# R2P_DCM_v2.net
KiCad netlist of a schematic drawn in EAGLE
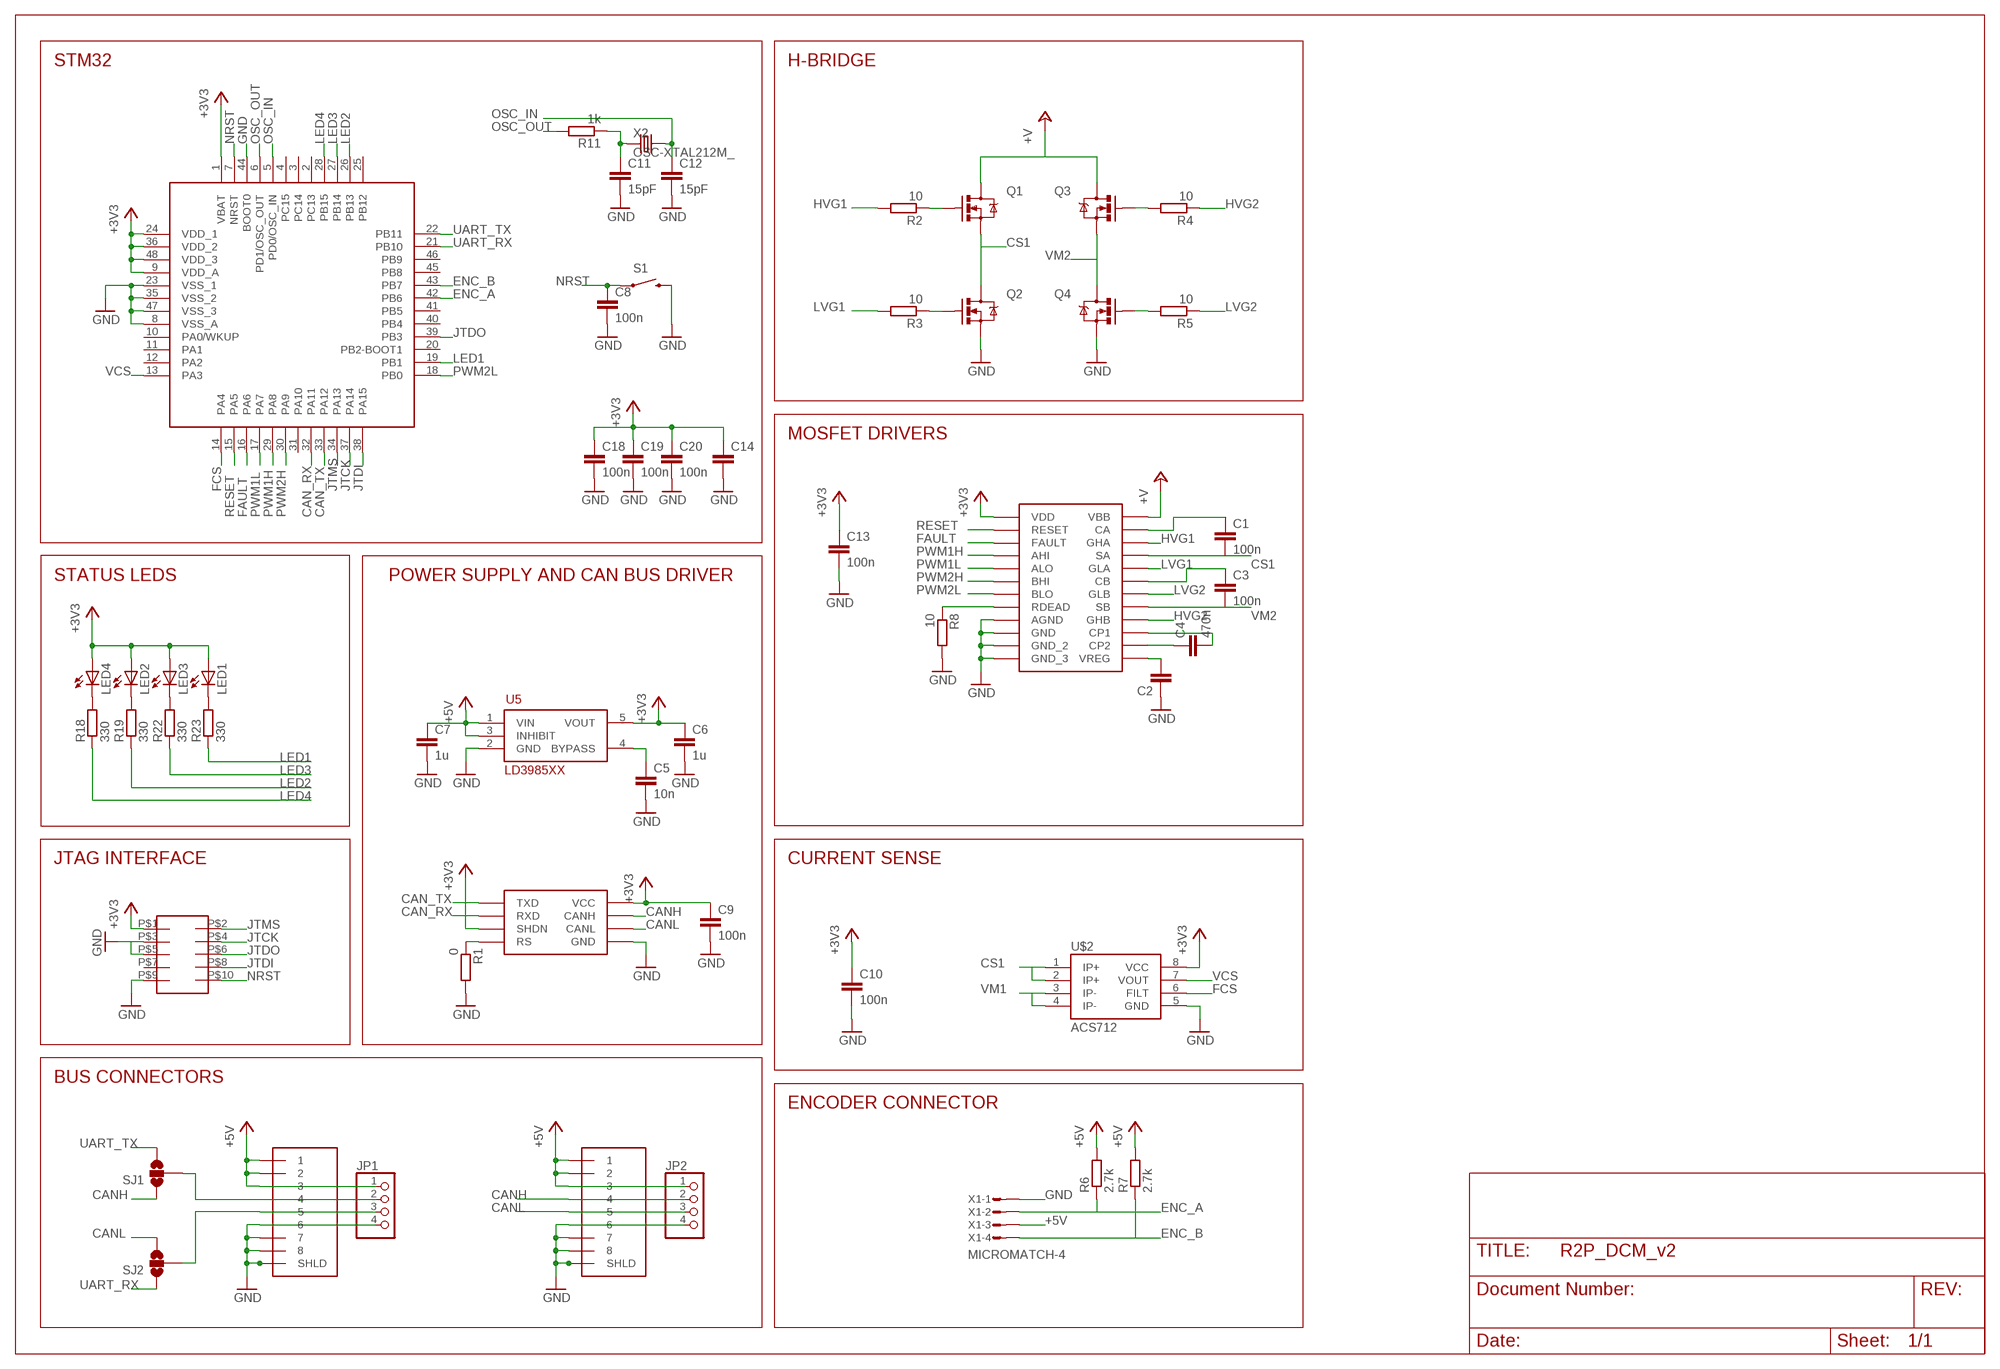
[diagram p0: schematic, sheet 1]

(export (version "E")
  (design (tool "Eeschema 10.0.6"))
  (components
    (comp (ref "1")
      (value "RJ45-43860")
      (footprint "eagle-import:0438600010")
      (libsource (lib "eagle-import") (part "RJ45-43860"))
    )
    (comp (ref "2")
      (value "RJ45-43860")
      (footprint "eagle-import:0438600010")
      (libsource (lib "eagle-import") (part "RJ45-43860"))
    )
    (comp (ref "C1")
      (value "100n")
      (footprint "eagle-import:C0603")
      (libsource (lib "eagle-import") (part "C-EUC0603"))
    )
    (comp (ref "C2")
      (value "C-EUC0805")
      (footprint "eagle-import:C0805")
      (libsource (lib "eagle-import") (part "C-EUC0805"))
    )
    (comp (ref "C3")
      (value "100n")
      (footprint "eagle-import:C0603")
      (libsource (lib "eagle-import") (part "C-EUC0603"))
    )
    (comp (ref "C4")
      (value "470n")
      (footprint "eagle-import:C0603")
      (libsource (lib "eagle-import") (part "C-EUC0603"))
    )
    (comp (ref "C5")
      (value "10n")
      (footprint "eagle-import:C0603")
      (libsource (lib "eagle-import") (part "C-EUC0603"))
    )
    (comp (ref "C6")
      (value "1u")
      (footprint "eagle-import:C0603")
      (libsource (lib "eagle-import") (part "C-EUC0603"))
    )
    (comp (ref "C7")
      (value "1u")
      (footprint "eagle-import:C0603")
      (libsource (lib "eagle-import") (part "C-EUC0603"))
    )
    (comp (ref "C8")
      (value "100n")
      (footprint "eagle-import:C0603")
      (libsource (lib "eagle-import") (part "C-EUC0603"))
    )
    (comp (ref "C9")
      (value "100n")
      (footprint "eagle-import:C0603")
      (libsource (lib "eagle-import") (part "C-EUC0603"))
    )
    (comp (ref "C10")
      (value "100n")
      (footprint "eagle-import:C0603")
      (libsource (lib "eagle-import") (part "C-EUC0603"))
    )
    (comp (ref "C11")
      (value "15pF")
      (footprint "eagle-import:C0603")
      (libsource (lib "eagle-import") (part "C-EUC0603"))
    )
    (comp (ref "C12")
      (value "15pF")
      (footprint "eagle-import:C0603")
      (libsource (lib "eagle-import") (part "C-EUC0603"))
    )
    (comp (ref "C13")
      (value "100n")
      (footprint "eagle-import:C0603")
      (libsource (lib "eagle-import") (part "C-EUC0603"))
    )
    (comp (ref "C14")
      (value "C-EUC0805")
      (footprint "eagle-import:C0805")
      (libsource (lib "eagle-import") (part "C-EUC0805"))
    )
    (comp (ref "C18")
      (value "100n")
      (footprint "eagle-import:C0603")
      (libsource (lib "eagle-import") (part "C-EUC0603"))
    )
    (comp (ref "C19")
      (value "100n")
      (footprint "eagle-import:C0603")
      (libsource (lib "eagle-import") (part "C-EUC0603"))
    )
    (comp (ref "C20")
      (value "100n")
      (footprint "eagle-import:C0603")
      (libsource (lib "eagle-import") (part "C-EUC0603"))
    )
    (comp (ref "JP1")
      (value "PINHD-1X4/90")
      (footprint "eagle-import:1X04_90")
      (libsource (lib "eagle-import") (part "PINHD-1X4/90"))
    )
    (comp (ref "JP2")
      (value "PINHD-1X4/90")
      (footprint "eagle-import:1X04_90")
      (libsource (lib "eagle-import") (part "PINHD-1X4/90"))
    )
    (comp (ref "LED1")
      (value "LEDCHIPLED_0805")
      (footprint "eagle-import:CHIPLED_0805")
      (libsource (lib "eagle-import") (part "LEDCHIPLED_0805"))
    )
    (comp (ref "LED2")
      (value "LEDCHIPLED_0805")
      (footprint "eagle-import:CHIPLED_0805")
      (libsource (lib "eagle-import") (part "LEDCHIPLED_0805"))
    )
    (comp (ref "LED3")
      (value "LEDCHIPLED_0805")
      (footprint "eagle-import:CHIPLED_0805")
      (libsource (lib "eagle-import") (part "LEDCHIPLED_0805"))
    )
    (comp (ref "LED4")
      (value "LEDCHIPLED_0805")
      (footprint "eagle-import:CHIPLED_0805")
      (libsource (lib "eagle-import") (part "LEDCHIPLED_0805"))
    )
    (comp (ref "Q1")
      (value "MOSFET-NCHANNELFDD8580")
      (footprint "eagle-import:DPAK")
      (libsource (lib "eagle-import") (part "MOSFET-NCHANNELFDD8580"))
    )
    (comp (ref "Q2")
      (value "MOSFET-NCHANNELFDD8580")
      (footprint "eagle-import:DPAK")
      (libsource (lib "eagle-import") (part "MOSFET-NCHANNELFDD8580"))
    )
    (comp (ref "Q3")
      (value "MOSFET-NCHANNELFDD8580")
      (footprint "eagle-import:DPAK")
      (libsource (lib "eagle-import") (part "MOSFET-NCHANNELFDD8580"))
    )
    (comp (ref "Q4")
      (value "MOSFET-NCHANNELFDD8580")
      (footprint "eagle-import:DPAK")
      (libsource (lib "eagle-import") (part "MOSFET-NCHANNELFDD8580"))
    )
    (comp (ref "R1")
      (value "0")
      (footprint "eagle-import:R0603")
      (libsource (lib "eagle-import") (part "R-EU_R0603"))
    )
    (comp (ref "R2")
      (value "10")
      (footprint "eagle-import:R0603")
      (libsource (lib "eagle-import") (part "R-EU_R0603"))
    )
    (comp (ref "R3")
      (value "10")
      (footprint "eagle-import:R0603")
      (libsource (lib "eagle-import") (part "R-EU_R0603"))
    )
    (comp (ref "R4")
      (value "10")
      (footprint "eagle-import:R0603")
      (libsource (lib "eagle-import") (part "R-EU_R0603"))
    )
    (comp (ref "R5")
      (value "10")
      (footprint "eagle-import:R0603")
      (libsource (lib "eagle-import") (part "R-EU_R0603"))
    )
    (comp (ref "R6")
      (value "2.7k")
      (footprint "eagle-import:R0603")
      (libsource (lib "eagle-import") (part "R-EU_R0603"))
    )
    (comp (ref "R7")
      (value "2.7k")
      (footprint "eagle-import:R0603")
      (libsource (lib "eagle-import") (part "R-EU_R0603"))
    )
    (comp (ref "R8")
      (value "10")
      (footprint "eagle-import:R0603")
      (libsource (lib "eagle-import") (part "R-EU_R0603"))
    )
    (comp (ref "R11")
      (value "1k")
      (footprint "eagle-import:R0603")
      (libsource (lib "eagle-import") (part "R-EU_R0603"))
    )
    (comp (ref "R18")
      (value "330")
      (footprint "eagle-import:R0603")
      (libsource (lib "eagle-import") (part "R-EU_R0603"))
    )
    (comp (ref "R19")
      (value "330")
      (footprint "eagle-import:R0603")
      (libsource (lib "eagle-import") (part "R-EU_R0603"))
    )
    (comp (ref "R22")
      (value "330")
      (footprint "eagle-import:R0603")
      (libsource (lib "eagle-import") (part "R-EU_R0603"))
    )
    (comp (ref "R23")
      (value "330")
      (footprint "eagle-import:R0603")
      (libsource (lib "eagle-import") (part "R-EU_R0603"))
    )
    (comp (ref "S1")
      (value "SWITCH-MOMENTARY-2-SMD-1101NE")
      (footprint "eagle-import:TACTILE-SWITCH-1101NE")
      (libsource (lib "eagle-import") (part "SWITCH-MOMENTARY-2-SMD-1101NE"))
    )
    (comp (ref "SJ1")
      (value "SOLDERJUMPER_2WAYPASTE1&2")
      (footprint "eagle-import:SJ_3_PASTE1&2")
      (libsource (lib "eagle-import") (part "SOLDERJUMPER_2WAYPASTE1&2"))
    )
    (comp (ref "SJ2")
      (value "SOLDERJUMPER_2WAYPASTE1&2")
      (footprint "eagle-import:SJ_3_PASTE1&2")
      (libsource (lib "eagle-import") (part "SOLDERJUMPER_2WAYPASTE1&2"))
    )
    (comp (ref "SOT1")
      (value "MAX3051")
      (footprint "eagle-import:SOT23-8L")
      (libsource (lib "eagle-import") (part "MAX3051"))
    )
    (comp (ref "U$1")
      (value "A4940")
      (footprint "eagle-import:TSSOP24")
      (libsource (lib "eagle-import") (part "A4940"))
    )
    (comp (ref "U$2")
      (value "ACS712")
      (footprint "eagle-import:SO08")
      (libsource (lib "eagle-import") (part "ACS712"))
    )
    (comp (ref "U$4")
      (value "FTSH-105")
      (footprint "eagle-import:FTSH-105")
      (libsource (lib "eagle-import") (part "FTSH-105"))
    )
    (comp (ref "U1")
      (value "STM32F103CX")
      (footprint "eagle-import:LQFP48")
      (libsource (lib "eagle-import") (part "STM32F103CX"))
    )
    (comp (ref "U5")
      (value "LD3985XX")
      (footprint "eagle-import:SOT23-5L")
      (libsource (lib "eagle-import") (part "LD3985XX"))
    )
    (comp (ref "X1")
      (value "MICROMATCH-4")
      (footprint "eagle-import:MICROMATCH-4")
      (libsource (lib "eagle-import") (part "MICROMATCH-4"))
    )
    (comp (ref "X2")
      (value "OSC-XTAL212M_")
      (footprint "eagle-import:4X6")
      (libsource (lib "eagle-import") (part "OSC-XTAL212M_"))
    )
  )
  (nets
    (net (code "1") (name "+3V3") (class "Default")
      (node (ref "C10") (pin "1") (pinfunction "1_1") (pintype "passive"))
      (node (ref "C13") (pin "1") (pinfunction "1_1") (pintype "passive"))
      (node (ref "C14") (pin "1") (pinfunction "1_1") (pintype "passive"))
      (node (ref "C18") (pin "1") (pinfunction "1_1") (pintype "passive"))
      (node (ref "C19") (pin "1") (pinfunction "1_1") (pintype "passive"))
      (node (ref "C20") (pin "1") (pinfunction "1_1") (pintype "passive"))
      (node (ref "C6") (pin "1") (pinfunction "1_1") (pintype "passive"))
      (node (ref "C9") (pin "1") (pinfunction "1_1") (pintype "passive"))
      (node (ref "LED1") (pin "A") (pinfunction "A_A") (pintype "passive"))
      (node (ref "LED2") (pin "A") (pinfunction "A_A") (pintype "passive"))
      (node (ref "LED3") (pin "A") (pinfunction "A_A") (pintype "passive"))
      (node (ref "LED4") (pin "A") (pinfunction "A_A") (pintype "passive"))
      (node (ref "SOT1") (pin "P$3") (pinfunction "VCC_P$3") (pintype "bidirectional"))
      (node (ref "SOT1") (pin "P$5") (pinfunction "SHDN_P$5") (pintype "bidirectional"))
      (node (ref "U$1") (pin "21") (pinfunction "VDD_21") (pintype "bidirectional"))
      (node (ref "U$2") (pin "8") (pinfunction "VCC_8") (pintype "bidirectional"))
      (node (ref "U$4") (pin "P$1") (pinfunction "P$1_P$1") (pintype "bidirectional"))
      (node (ref "U1") (pin "1") (pinfunction "VBAT_1") (pintype "bidirectional"))
      (node (ref "U1") (pin "24") (pinfunction "VDD_1_24") (pintype "bidirectional"))
      (node (ref "U1") (pin "36") (pinfunction "VDD_2_36") (pintype "bidirectional"))
      (node (ref "U1") (pin "48") (pinfunction "VDD_3_48") (pintype "bidirectional"))
      (node (ref "U1") (pin "9") (pinfunction "VDD_A_9") (pintype "bidirectional"))
      (node (ref "U5") (pin "5") (pinfunction "VOUT_5") (pintype "bidirectional"))
    )
    (net (code "2") (name "+5V") (class "Default")
      (node (ref "1") (pin "P$1") (pinfunction "1_P$1") (pintype "bidirectional"))
      (node (ref "1") (pin "P$2") (pinfunction "2_P$2") (pintype "bidirectional"))
      (node (ref "1") (pin "P$3") (pinfunction "3_P$3") (pintype "bidirectional"))
      (node (ref "2") (pin "P$1") (pinfunction "1_P$1") (pintype "bidirectional"))
      (node (ref "2") (pin "P$2") (pinfunction "2_P$2") (pintype "bidirectional"))
      (node (ref "2") (pin "P$3") (pinfunction "3_P$3") (pintype "bidirectional"))
      (node (ref "C7") (pin "1") (pinfunction "1_1") (pintype "passive"))
      (node (ref "JP1") (pin "1") (pinfunction "1_1") (pintype "passive"))
      (node (ref "JP2") (pin "1") (pinfunction "1_1") (pintype "passive"))
      (node (ref "R6") (pin "2") (pinfunction "2_2") (pintype "passive"))
      (node (ref "R7") (pin "2") (pinfunction "2_2") (pintype "passive"))
      (node (ref "U5") (pin "1") (pinfunction "VIN_1") (pintype "bidirectional"))
      (node (ref "U5") (pin "3") (pinfunction "INHIBIT_3") (pintype "bidirectional"))
      (node (ref "X1") (pin "3") (pinfunction "S_3") (pintype "passive"))
    )
    (net (code "3") (name "+V") (class "Default")
      (node (ref "Q1") (pin "4") (pinfunction "D_4") (pintype "passive"))
      (node (ref "Q3") (pin "4") (pinfunction "D_4") (pintype "passive"))
      (node (ref "U$1") (pin "12") (pinfunction "VBB_12") (pintype "bidirectional"))
    )
    (net (code "4") (name "/CANH") (class "Default")
      (node (ref "2") (pin "P$4") (pinfunction "4_P$4") (pintype "bidirectional"))
      (node (ref "JP2") (pin "2") (pinfunction "2_2") (pintype "passive"))
      (node (ref "SJ1") (pin "1") (pinfunction "1_1") (pintype "passive"))
      (node (ref "SOT1") (pin "P$7") (pinfunction "CANH_P$7") (pintype "bidirectional"))
    )
    (net (code "5") (name "/CANL") (class "Default")
      (node (ref "2") (pin "P$5") (pinfunction "5_P$5") (pintype "bidirectional"))
      (node (ref "JP2") (pin "3") (pinfunction "3_3") (pintype "passive"))
      (node (ref "SJ2") (pin "3") (pinfunction "3_3") (pintype "passive"))
      (node (ref "SOT1") (pin "P$6") (pinfunction "CANL_P$6") (pintype "bidirectional"))
    )
    (net (code "6") (name "/CAN_RX") (class "Default")
      (node (ref "SOT1") (pin "P$4") (pinfunction "RXD_P$4") (pintype "bidirectional"))
      (node (ref "U1") (pin "32") (pinfunction "PA11_32") (pintype "bidirectional"))
    )
    (net (code "7") (name "/CAN_TX") (class "Default")
      (node (ref "SOT1") (pin "P$1") (pinfunction "TXD_P$1") (pintype "bidirectional"))
      (node (ref "U1") (pin "33") (pinfunction "PA12_33") (pintype "bidirectional"))
    )
    (net (code "8") (name "/CS1") (class "Default")
      (node (ref "C1") (pin "2") (pinfunction "2_2") (pintype "passive"))
      (node (ref "Q1") (pin "3") (pinfunction "S_3") (pintype "passive"))
      (node (ref "Q2") (pin "4") (pinfunction "D_4") (pintype "passive"))
      (node (ref "U$1") (pin "10") (pinfunction "SA_10") (pintype "bidirectional"))
      (node (ref "U$2") (pin "1") (pinfunction "IP+_1") (pintype "bidirectional"))
      (node (ref "U$2") (pin "2") (pinfunction "IP+_2") (pintype "bidirectional"))
    )
    (net (code "9") (name "/ENC_A") (class "Default")
      (node (ref "R6") (pin "1") (pinfunction "1_1") (pintype "passive"))
      (node (ref "U1") (pin "42") (pinfunction "PB6_42") (pintype "bidirectional"))
      (node (ref "X1") (pin "2") (pinfunction "S_2") (pintype "passive"))
    )
    (net (code "10") (name "/ENC_B") (class "Default")
      (node (ref "R7") (pin "1") (pinfunction "1_1") (pintype "passive"))
      (node (ref "U1") (pin "43") (pinfunction "PB7_43") (pintype "bidirectional"))
      (node (ref "X1") (pin "4") (pinfunction "S_4") (pintype "passive"))
    )
    (net (code "11") (name "/FAULT") (class "Default")
      (node (ref "U$1") (pin "24") (pinfunction "FAULT_24") (pintype "bidirectional"))
      (node (ref "U1") (pin "16") (pinfunction "PA6_16") (pintype "bidirectional"))
    )
    (net (code "12") (name "/FCS") (class "Default")
      (node (ref "U$2") (pin "6") (pinfunction "FILT_6") (pintype "bidirectional"))
      (node (ref "U1") (pin "14") (pinfunction "PA4_14") (pintype "bidirectional"))
    )
    (net (code "13") (name "/HVG1") (class "Default")
      (node (ref "R2") (pin "2") (pinfunction "2_2") (pintype "passive"))
      (node (ref "U$1") (pin "9") (pinfunction "GHA_9") (pintype "bidirectional"))
    )
    (net (code "14") (name "/HVG2") (class "Default")
      (node (ref "R4") (pin "1") (pinfunction "1_1") (pintype "passive"))
      (node (ref "U$1") (pin "5") (pinfunction "GHB_5") (pintype "bidirectional"))
    )
    (net (code "15") (name "/JTCK") (class "Default")
      (node (ref "U$4") (pin "P$4") (pinfunction "P$4_P$4") (pintype "bidirectional"))
      (node (ref "U1") (pin "37") (pinfunction "PA14_37") (pintype "bidirectional"))
    )
    (net (code "16") (name "/JTDI") (class "Default")
      (node (ref "U$4") (pin "P$8") (pinfunction "P$8_P$8") (pintype "bidirectional"))
      (node (ref "U1") (pin "38") (pinfunction "PA15_38") (pintype "bidirectional"))
    )
    (net (code "17") (name "/JTDO") (class "Default")
      (node (ref "U$4") (pin "P$6") (pinfunction "P$6_P$6") (pintype "bidirectional"))
      (node (ref "U1") (pin "39") (pinfunction "PB3_39") (pintype "bidirectional"))
    )
    (net (code "18") (name "/JTMS") (class "Default")
      (node (ref "U$4") (pin "P$2") (pinfunction "P$2_P$2") (pintype "bidirectional"))
      (node (ref "U1") (pin "34") (pinfunction "PA13_34") (pintype "bidirectional"))
    )
    (net (code "19") (name "/LED1") (class "Default")
      (node (ref "R23") (pin "1") (pinfunction "1_1") (pintype "passive"))
      (node (ref "U1") (pin "19") (pinfunction "PB1_19") (pintype "bidirectional"))
    )
    (net (code "20") (name "/LED2") (class "Default")
      (node (ref "R19") (pin "1") (pinfunction "1_1") (pintype "passive"))
      (node (ref "U1") (pin "26") (pinfunction "PB13_26") (pintype "bidirectional"))
    )
    (net (code "21") (name "/LED3") (class "Default")
      (node (ref "R22") (pin "1") (pinfunction "1_1") (pintype "passive"))
      (node (ref "U1") (pin "27") (pinfunction "PB14_27") (pintype "bidirectional"))
    )
    (net (code "22") (name "/LED4") (class "Default")
      (node (ref "R18") (pin "1") (pinfunction "1_1") (pintype "passive"))
      (node (ref "U1") (pin "28") (pinfunction "PB15_28") (pintype "bidirectional"))
    )
    (net (code "23") (name "/LVG1") (class "Default")
      (node (ref "R3") (pin "2") (pinfunction "2_2") (pintype "passive"))
      (node (ref "U$1") (pin "11") (pinfunction "GLA_11") (pintype "bidirectional"))
    )
    (net (code "24") (name "/LVG2") (class "Default")
      (node (ref "R5") (pin "1") (pinfunction "1_1") (pintype "passive"))
      (node (ref "U$1") (pin "3") (pinfunction "GLB_3") (pintype "bidirectional"))
    )
    (net (code "25") (name "/NRST") (class "Default")
      (node (ref "C8") (pin "1") (pinfunction "1_1") (pintype "passive"))
      (node (ref "S1") (pin "P$1") (pinfunction "1_P$1") (pintype "passive"))
      (node (ref "U$4") (pin "P$10") (pinfunction "P$10_P$10") (pintype "bidirectional"))
      (node (ref "U1") (pin "7") (pinfunction "NRST_7") (pintype "bidirectional"))
    )
    (net (code "26") (name "/OSC_IN") (class "Default")
      (node (ref "C12") (pin "1") (pinfunction "1_1") (pintype "passive"))
      (node (ref "U1") (pin "5") (pinfunction "PD0/OSC_IN_5") (pintype "bidirectional"))
      (node (ref "X2") (pin "2") (pinfunction "X2_2") (pintype "bidirectional"))
    )
    (net (code "27") (name "/OSC_OUT") (class "Default")
      (node (ref "R11") (pin "2") (pinfunction "2_2") (pintype "passive"))
      (node (ref "U1") (pin "6") (pinfunction "PD1/OSC_OUT_6") (pintype "bidirectional"))
    )
    (net (code "28") (name "/PWM1H") (class "Default")
      (node (ref "U$1") (pin "20") (pinfunction "AHI_20") (pintype "bidirectional"))
      (node (ref "U1") (pin "29") (pinfunction "PA8_29") (pintype "bidirectional"))
    )
    (net (code "29") (name "/PWM1L") (class "Default")
      (node (ref "U$1") (pin "19") (pinfunction "ALO_19") (pintype "bidirectional"))
      (node (ref "U1") (pin "17") (pinfunction "PA7_17") (pintype "bidirectional"))
    )
    (net (code "30") (name "/PWM2H") (class "Default")
      (node (ref "U$1") (pin "18") (pinfunction "BHI_18") (pintype "bidirectional"))
      (node (ref "U1") (pin "30") (pinfunction "PA9_30") (pintype "bidirectional"))
    )
    (net (code "31") (name "/PWM2L") (class "Default")
      (node (ref "U$1") (pin "17") (pinfunction "BLO_17") (pintype "bidirectional"))
      (node (ref "U1") (pin "18") (pinfunction "PB0_18") (pintype "bidirectional"))
    )
    (net (code "32") (name "/RESET") (class "Default")
      (node (ref "U$1") (pin "1") (pinfunction "RESET_1") (pintype "bidirectional"))
      (node (ref "U1") (pin "15") (pinfunction "PA5_15") (pintype "bidirectional"))
    )
    (net (code "33") (name "/UART_RX") (class "Default")
      (node (ref "SJ2") (pin "1") (pinfunction "1_1") (pintype "passive"))
      (node (ref "U1") (pin "21") (pinfunction "PB10_21") (pintype "bidirectional"))
    )
    (net (code "34") (name "/UART_TX") (class "Default")
      (node (ref "SJ1") (pin "3") (pinfunction "3_3") (pintype "passive"))
      (node (ref "U1") (pin "22") (pinfunction "PB11_22") (pintype "bidirectional"))
    )
    (net (code "35") (name "/VCS") (class "Default")
      (node (ref "U$2") (pin "7") (pinfunction "VOUT_7") (pintype "bidirectional"))
      (node (ref "U1") (pin "13") (pinfunction "PA3_13") (pintype "bidirectional"))
    )
    (net (code "36") (name "/VM1") (class "Default")
      (node (ref "U$2") (pin "3") (pinfunction "IP-_3") (pintype "bidirectional"))
      (node (ref "U$2") (pin "4") (pinfunction "IP-_4") (pintype "bidirectional"))
    )
    (net (code "37") (name "/VM2") (class "Default")
      (node (ref "C3") (pin "2") (pinfunction "2_2") (pintype "passive"))
      (node (ref "Q3") (pin "3") (pinfunction "S_3") (pintype "passive"))
      (node (ref "Q4") (pin "4") (pinfunction "D_4") (pintype "passive"))
      (node (ref "U$1") (pin "4") (pinfunction "SB_4") (pintype "bidirectional"))
    )
    (net (code "38") (name "GND") (class "Default")
      (node (ref "1") (pin "P$10") (pinfunction "P$1_P$10") (pintype "power_in"))
      (node (ref "1") (pin "P$6") (pinfunction "6_P$6") (pintype "bidirectional"))
      (node (ref "1") (pin "P$7") (pinfunction "7_P$7") (pintype "bidirectional"))
      (node (ref "1") (pin "P$8") (pinfunction "8_P$8") (pintype "bidirectional"))
      (node (ref "1") (pin "P$9") (pinfunction "SHLD_P$9") (pintype "power_in"))
      (node (ref "2") (pin "P$10") (pinfunction "P$1_P$10") (pintype "power_in"))
      (node (ref "2") (pin "P$6") (pinfunction "6_P$6") (pintype "bidirectional"))
      (node (ref "2") (pin "P$7") (pinfunction "7_P$7") (pintype "bidirectional"))
      (node (ref "2") (pin "P$8") (pinfunction "8_P$8") (pintype "bidirectional"))
      (node (ref "2") (pin "P$9") (pinfunction "SHLD_P$9") (pintype "power_in"))
      (node (ref "C10") (pin "2") (pinfunction "2_2") (pintype "passive"))
      (node (ref "C11") (pin "2") (pinfunction "2_2") (pintype "passive"))
      (node (ref "C12") (pin "2") (pinfunction "2_2") (pintype "passive"))
      (node (ref "C13") (pin "2") (pinfunction "2_2") (pintype "passive"))
      (node (ref "C14") (pin "2") (pinfunction "2_2") (pintype "passive"))
      (node (ref "C18") (pin "2") (pinfunction "2_2") (pintype "passive"))
      (node (ref "C19") (pin "2") (pinfunction "2_2") (pintype "passive"))
      (node (ref "C2") (pin "1") (pinfunction "1_1") (pintype "passive"))
      (node (ref "C20") (pin "2") (pinfunction "2_2") (pintype "passive"))
      (node (ref "C5") (pin "2") (pinfunction "2_2") (pintype "passive"))
      (node (ref "C6") (pin "2") (pinfunction "2_2") (pintype "passive"))
      (node (ref "C7") (pin "2") (pinfunction "2_2") (pintype "passive"))
      (node (ref "C8") (pin "2") (pinfunction "2_2") (pintype "passive"))
      (node (ref "C9") (pin "2") (pinfunction "2_2") (pintype "passive"))
      (node (ref "JP1") (pin "4") (pinfunction "4_4") (pintype "passive"))
      (node (ref "JP2") (pin "4") (pinfunction "4_4") (pintype "passive"))
      (node (ref "Q2") (pin "3") (pinfunction "S_3") (pintype "passive"))
      (node (ref "Q4") (pin "3") (pinfunction "S_3") (pintype "passive"))
      (node (ref "R1") (pin "2") (pinfunction "2_2") (pintype "passive"))
      (node (ref "R8") (pin "2") (pinfunction "2_2") (pintype "passive"))
      (node (ref "S1") (pin "P$2") (pinfunction "2_P$2") (pintype "passive"))
      (node (ref "SOT1") (pin "P$2") (pinfunction "GND_P$2") (pintype "bidirectional"))
      (node (ref "U$1") (pin "15") (pinfunction "GND_2_15") (pintype "bidirectional"))
      (node (ref "U$1") (pin "16") (pinfunction "GND_3_16") (pintype "bidirectional"))
      (node (ref "U$1") (pin "2") (pinfunction "GND_2") (pintype "bidirectional"))
      (node (ref "U$1") (pin "22") (pinfunction "AGND_22") (pintype "bidirectional"))
      (node (ref "U$1") (pin "PAD") (pinfunction "GND_PAD") (pintype "bidirectional"))
      (node (ref "U$2") (pin "5") (pinfunction "GND_5") (pintype "bidirectional"))
      (node (ref "U$4") (pin "P$3") (pinfunction "P$3_P$3") (pintype "bidirectional"))
      (node (ref "U$4") (pin "P$9") (pinfunction "P$9_P$9") (pintype "bidirectional"))
      (node (ref "U1") (pin "23") (pinfunction "VSS_1_23") (pintype "bidirectional"))
      (node (ref "U1") (pin "35") (pinfunction "VSS_2_35") (pintype "bidirectional"))
      (node (ref "U1") (pin "44") (pinfunction "BOOT0_44") (pintype "bidirectional"))
      (node (ref "U1") (pin "47") (pinfunction "VSS_3_47") (pintype "bidirectional"))
      (node (ref "U1") (pin "8") (pinfunction "VSS_A_8") (pintype "bidirectional"))
      (node (ref "U5") (pin "2") (pinfunction "GND_2") (pintype "bidirectional"))
      (node (ref "X1") (pin "1") (pinfunction "S_1") (pintype "passive"))
    )
    (net (code "39") (name "Net-(1-4)") (class "Default")
      (node (ref "1") (pin "P$4") (pinfunction "4_P$4") (pintype "bidirectional"))
      (node (ref "JP1") (pin "2") (pinfunction "2_2") (pintype "passive"))
      (node (ref "SJ1") (pin "2") (pinfunction "2_2") (pintype "passive"))
    )
    (net (code "40") (name "Net-(1-5)") (class "Default")
      (node (ref "1") (pin "P$5") (pinfunction "5_P$5") (pintype "bidirectional"))
      (node (ref "JP1") (pin "3") (pinfunction "3_3") (pintype "passive"))
      (node (ref "SJ2") (pin "2") (pinfunction "2_2") (pintype "passive"))
    )
    (net (code "41") (name "Net-(LED1-PadC)") (class "Default")
      (node (ref "LED1") (pin "C") (pinfunction "C_C") (pintype "passive"))
      (node (ref "R23") (pin "2") (pinfunction "2_2") (pintype "passive"))
    )
    (net (code "42") (name "Net-(LED2-PadC)") (class "Default")
      (node (ref "LED2") (pin "C") (pinfunction "C_C") (pintype "passive"))
      (node (ref "R19") (pin "2") (pinfunction "2_2") (pintype "passive"))
    )
    (net (code "43") (name "Net-(LED3-PadC)") (class "Default")
      (node (ref "LED3") (pin "C") (pinfunction "C_C") (pintype "passive"))
      (node (ref "R22") (pin "2") (pinfunction "2_2") (pintype "passive"))
    )
    (net (code "44") (name "Net-(LED4-PadC)") (class "Default")
      (node (ref "LED4") (pin "C") (pinfunction "C_C") (pintype "passive"))
      (node (ref "R18") (pin "2") (pinfunction "2_2") (pintype "passive"))
    )
    (net (code "45") (name "Net-(Q1-G)") (class "Default")
      (node (ref "Q1") (pin "1") (pinfunction "G_1") (pintype "passive"))
      (node (ref "R2") (pin "1") (pinfunction "1_1") (pintype "passive"))
    )
    (net (code "46") (name "Net-(Q2-G)") (class "Default")
      (node (ref "Q2") (pin "1") (pinfunction "G_1") (pintype "passive"))
      (node (ref "R3") (pin "1") (pinfunction "1_1") (pintype "passive"))
    )
    (net (code "47") (name "Net-(Q3-G)") (class "Default")
      (node (ref "Q3") (pin "1") (pinfunction "G_1") (pintype "passive"))
      (node (ref "R4") (pin "2") (pinfunction "2_2") (pintype "passive"))
    )
    (net (code "48") (name "Net-(Q4-G)") (class "Default")
      (node (ref "Q4") (pin "1") (pinfunction "G_1") (pintype "passive"))
      (node (ref "R5") (pin "2") (pinfunction "2_2") (pintype "passive"))
    )
    (net (code "49") (name "Net-(SOT1-RS)") (class "Default")
      (node (ref "R1") (pin "1") (pinfunction "1_1") (pintype "passive"))
      (node (ref "SOT1") (pin "P$8") (pinfunction "RS_P$8") (pintype "bidirectional"))
    )
    (net (code "50") (name "Net-(U$1-CA)") (class "Default")
      (node (ref "C1") (pin "1") (pinfunction "1_1") (pintype "passive"))
      (node (ref "U$1") (pin "8") (pinfunction "CA_8") (pintype "bidirectional"))
    )
    (net (code "51") (name "Net-(U$1-CB)") (class "Default")
      (node (ref "C3") (pin "1") (pinfunction "1_1") (pintype "passive"))
      (node (ref "U$1") (pin "6") (pinfunction "CB_6") (pintype "bidirectional"))
    )
    (net (code "52") (name "Net-(U$1-CP1)") (class "Default")
      (node (ref "C4") (pin "2") (pinfunction "2_2") (pintype "passive"))
      (node (ref "U$1") (pin "14") (pinfunction "CP1_14") (pintype "bidirectional"))
    )
    (net (code "53") (name "Net-(U$1-CP2)") (class "Default")
      (node (ref "C4") (pin "1") (pinfunction "1_1") (pintype "passive"))
      (node (ref "U$1") (pin "13") (pinfunction "CP2_13") (pintype "bidirectional"))
    )
    (net (code "54") (name "Net-(U$1-RDEAD)") (class "Default")
      (node (ref "R8") (pin "1") (pinfunction "1_1") (pintype "passive"))
      (node (ref "U$1") (pin "23") (pinfunction "RDEAD_23") (pintype "bidirectional"))
    )
    (net (code "55") (name "Net-(U$1-VREG)") (class "Default")
      (node (ref "C2") (pin "2") (pinfunction "2_2") (pintype "passive"))
      (node (ref "U$1") (pin "7") (pinfunction "VREG_7") (pintype "bidirectional"))
    )
    (net (code "56") (name "Net-(U5-BYPASS)") (class "Default")
      (node (ref "C5") (pin "1") (pinfunction "1_1") (pintype "passive"))
      (node (ref "U5") (pin "4") (pinfunction "BYPASS_4") (pintype "bidirectional"))
    )
    (net (code "57") (name "Net-(X2-X1)") (class "Default")
      (node (ref "C11") (pin "1") (pinfunction "1_1") (pintype "passive"))
      (node (ref "R11") (pin "1") (pinfunction "1_1") (pintype "passive"))
      (node (ref "X2") (pin "1") (pinfunction "X1_1") (pintype "bidirectional"))
    )
    (net (code "58") (name "unconnected-(U$4-PadP$5)") (class "Default")
      (node (ref "U$4") (pin "P$5") (pinfunction "P$5_P$5") (pintype "bidirectional"))
    )
    (net (code "59") (name "unconnected-(U$4-PadP$7)") (class "Default")
      (node (ref "U$4") (pin "P$7") (pinfunction "P$7_P$7") (pintype "bidirectional"))
    )
    (net (code "60") (name "unconnected-(U1-PA0{slash}WKUP-Pad10)") (class "Default")
      (node (ref "U1") (pin "10") (pinfunction "PA0/WKUP_10") (pintype "bidirectional"))
    )
    (net (code "61") (name "unconnected-(U1-PA1-Pad11)") (class "Default")
      (node (ref "U1") (pin "11") (pinfunction "PA1_11") (pintype "bidirectional"))
    )
    (net (code "62") (name "unconnected-(U1-PA2-Pad12)") (class "Default")
      (node (ref "U1") (pin "12") (pinfunction "PA2_12") (pintype "bidirectional"))
    )
    (net (code "63") (name "unconnected-(U1-PA10-Pad31)") (class "Default")
      (node (ref "U1") (pin "31") (pinfunction "PA10_31") (pintype "bidirectional"))
    )
    (net (code "64") (name "unconnected-(U1-PB2-BOOT1-Pad20)") (class "Default")
      (node (ref "U1") (pin "20") (pinfunction "PB2-BOOT1_20") (pintype "bidirectional"))
    )
    (net (code "65") (name "unconnected-(U1-PB4-Pad40)") (class "Default")
      (node (ref "U1") (pin "40") (pinfunction "PB4_40") (pintype "bidirectional"))
    )
    (net (code "66") (name "unconnected-(U1-PB5-Pad41)") (class "Default")
      (node (ref "U1") (pin "41") (pinfunction "PB5_41") (pintype "bidirectional"))
    )
    (net (code "67") (name "unconnected-(U1-PB8-Pad45)") (class "Default")
      (node (ref "U1") (pin "45") (pinfunction "PB8_45") (pintype "bidirectional"))
    )
    (net (code "68") (name "unconnected-(U1-PB9-Pad46)") (class "Default")
      (node (ref "U1") (pin "46") (pinfunction "PB9_46") (pintype "bidirectional"))
    )
    (net (code "69") (name "unconnected-(U1-PB12-Pad25)") (class "Default")
      (node (ref "U1") (pin "25") (pinfunction "PB12_25") (pintype "bidirectional"))
    )
    (net (code "70") (name "unconnected-(U1-PC13-Pad2)") (class "Default")
      (node (ref "U1") (pin "2") (pinfunction "PC13_2") (pintype "bidirectional"))
    )
    (net (code "71") (name "unconnected-(U1-PC14-Pad3)") (class "Default")
      (node (ref "U1") (pin "3") (pinfunction "PC14_3") (pintype "bidirectional"))
    )
    (net (code "72") (name "unconnected-(U1-PC15-Pad4)") (class "Default")
      (node (ref "U1") (pin "4") (pinfunction "PC15_4") (pintype "bidirectional"))
    )
  )
)
